# MSB.net
KiCad netlist of a schematic drawn in EasyEDA Pro
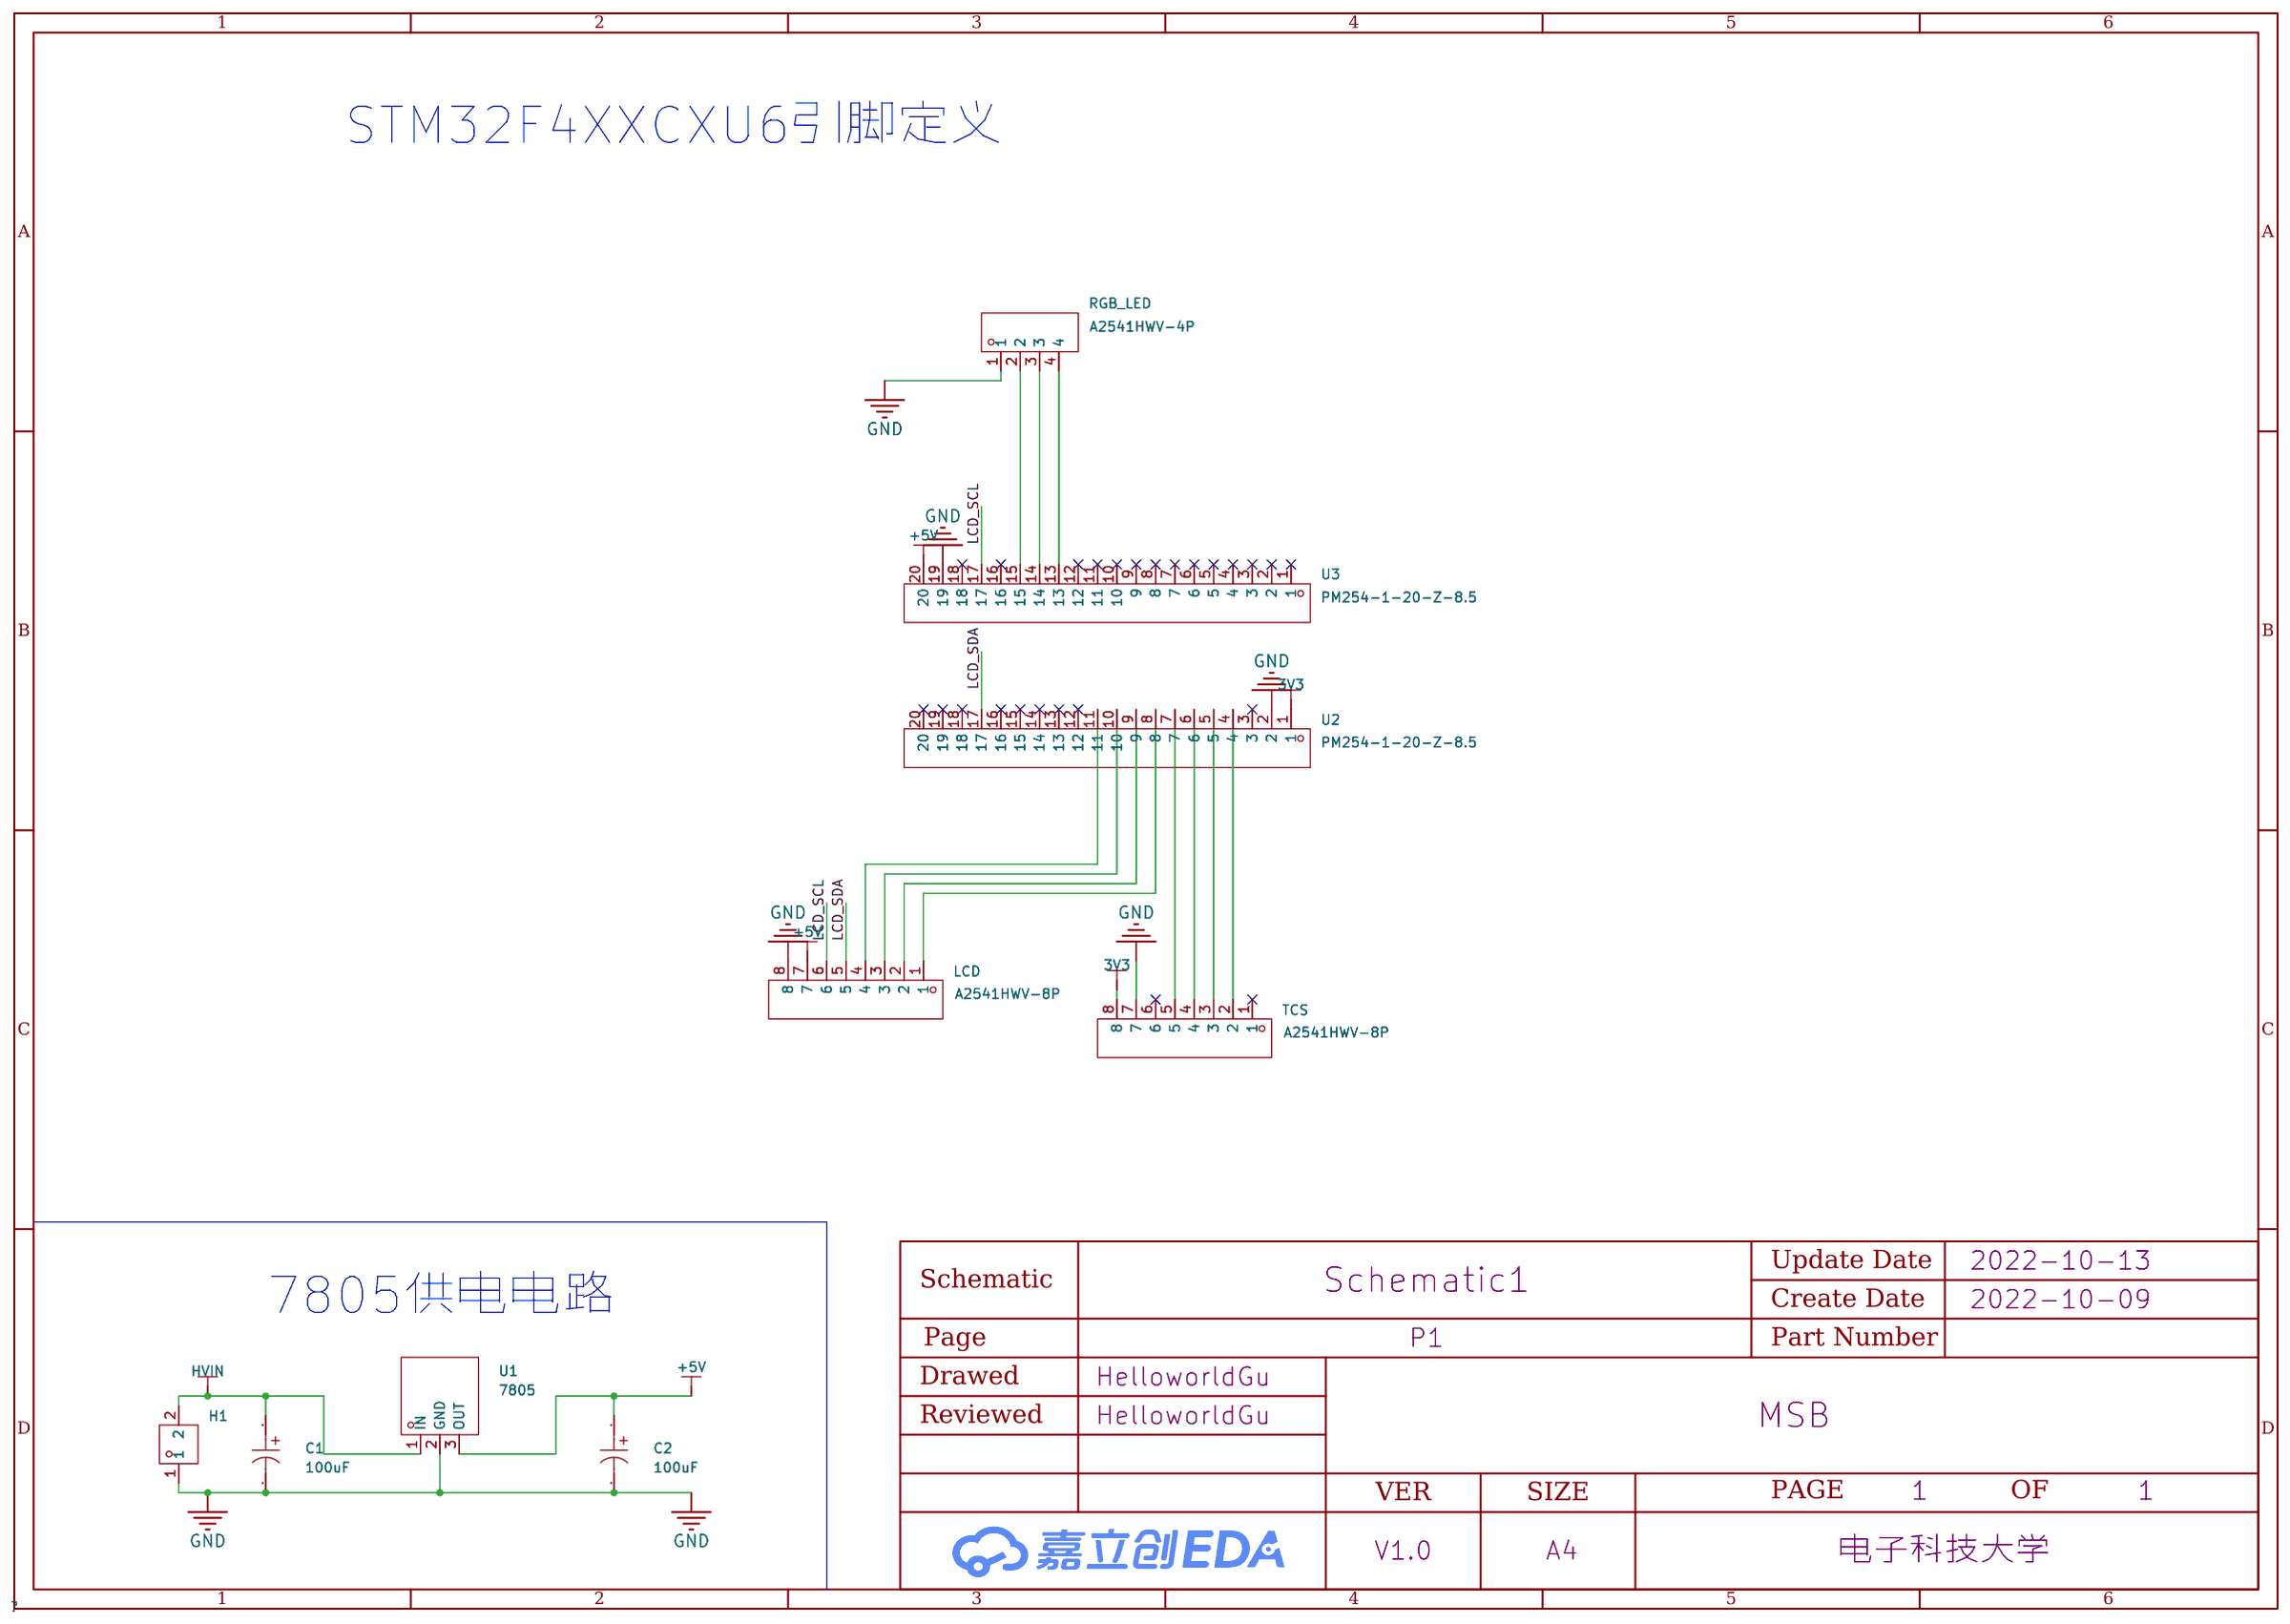
[diagram p0: schematic sheet]

(export (version "E")
  (design (tool "Eeschema 10.0.6"))
  (components
    (comp (ref "C1")
      (value "100uF")
      (footprint "easyedapro:CAP-TH_BD6.3-P2.50-D0.5-FD")
      (description "容值:100uF;精度:±20%;额定电压:35V;电容体直径:-;电容体长度:-;脚间距:-;纹波电流:-;等效串联电阻:-;工作寿命:-;")
      (fields
        (field (name "Manufacturer Part") "ECF1VM101E12OTPO")
        (field (name "Manufacturer") "Yunxing(云星)")
      )
      (libsource (lib "easyedapro") (part "ECF1VM101E12OTPO"))
    )
    (comp (ref "C2")
      (value "100uF")
      (footprint "easyedapro:CAP-TH_BD6.3-P2.50-D0.5-FD")
      (description "容值:100uF;精度:±20%;额定电压:35V;电容体直径:-;电容体长度:-;脚间距:-;纹波电流:-;等效串联电阻:-;工作寿命:-;")
      (fields
        (field (name "Manufacturer Part") "ECF1VM101E12OTPO")
        (field (name "Manufacturer") "Yunxing(云星)")
      )
      (libsource (lib "easyedapro") (part "ECF1VM101E12OTPO"))
    )
    (comp (ref "H1")
      (value "X6521WV-2x01H-C30D60")
      (footprint "easyedapro:HDR-TH_2P-P2.54-V-M")
      (fields (field (name "Manufacturer") "XKB Connectivity(中国星坤)"))
      (libsource (lib "easyedapro") (part "X6521WV-2X01H-C30D60"))
    )
    (comp (ref "LCD")
      (value "A2541HWV-8P")
      (footprint "easyedapro:HDR-TH_8P-P2.54-V-F")
      (fields (field (name "Manufacturer") "CJT(长江连接器)"))
      (libsource (lib "easyedapro") (part "A2541HWV-8P_C5149225"))
    )
    (comp (ref "RGB_LED")
      (value "A2541HWV-4P")
      (footprint "easyedapro:HDR-TH_4P-P2.54-V-F")
      (fields (field (name "Manufacturer") "CJT(长江连接器)"))
      (libsource (lib "easyedapro") (part "A2541HWV-4P_C5176037"))
    )
    (comp (ref "TCS")
      (value "A2541HWV-8P")
      (footprint "easyedapro:HDR-TH_8P-P2.54-V-F")
      (fields (field (name "Manufacturer") "CJT(长江连接器)"))
      (libsource (lib "easyedapro") (part "A2541HWV-8P_C5149225"))
    )
    (comp (ref "U1")
      (value "7805")
      (footprint "easyedapro:TO-220-3_L10.2-W4.5-P2.54-L-1")
      (fields (field (name "Manufacturer") "SY(顺烨）"))
      (libsource (lib "easyedapro") (part "7805_C4944936"))
    )
    (comp (ref "U2")
      (value "PM254-1-20-Z-8.5")
      (footprint "easyedapro:HDR-TH_20P-P2.54-V-F-2")
      (fields (field (name "Manufacturer") "HCTL(华灿天禄)"))
      (libsource (lib "easyedapro") (part "PM254-1-20-Z-8.5"))
    )
    (comp (ref "U3")
      (value "PM254-1-20-Z-8.5")
      (footprint "easyedapro:HDR-TH_20P-P2.54-V-F-2")
      (fields (field (name "Manufacturer") "HCTL(华灿天禄)"))
      (libsource (lib "easyedapro") (part "PM254-1-20-Z-8.5"))
    )
  )
  (nets
    (net (code "1") (name "+5V") (class "Default")
      (node (ref "C2") (pin "1") (pinfunction "1_1") (pintype "input"))
      (node (ref "LCD") (pin "7") (pinfunction "7_7") (pintype "input"))
      (node (ref "U1") (pin "3") (pinfunction "OUT_3") (pintype "input"))
      (node (ref "U3") (pin "20") (pinfunction "20_20") (pintype "input"))
    )
    (net (code "2") (name "/LCD_SCL") (class "Default")
      (node (ref "LCD") (pin "6") (pinfunction "6_6") (pintype "input"))
      (node (ref "U3") (pin "17") (pinfunction "17_17") (pintype "input"))
    )
    (net (code "3") (name "/LCD_SDA") (class "Default")
      (node (ref "LCD") (pin "5") (pinfunction "5_5") (pintype "input"))
      (node (ref "U2") (pin "17") (pinfunction "17_17") (pintype "input"))
    )
    (net (code "4") (name "3V3") (class "Default")
      (node (ref "TCS") (pin "8") (pinfunction "8_8") (pintype "input"))
      (node (ref "U2") (pin "1") (pinfunction "1_1") (pintype "input"))
    )
    (net (code "5") (name "GND") (class "Default")
      (node (ref "C1") (pin "2") (pinfunction "2_2") (pintype "input"))
      (node (ref "C2") (pin "2") (pinfunction "2_2") (pintype "input"))
      (node (ref "H1") (pin "1") (pinfunction "1_1") (pintype "input"))
      (node (ref "LCD") (pin "8") (pinfunction "8_8") (pintype "input"))
      (node (ref "RGB_LED") (pin "1") (pinfunction "1_1") (pintype "input"))
      (node (ref "TCS") (pin "7") (pinfunction "7_7") (pintype "input"))
      (node (ref "U1") (pin "2") (pinfunction "GND_2") (pintype "input"))
      (node (ref "U2") (pin "2") (pinfunction "2_2") (pintype "input"))
      (node (ref "U3") (pin "19") (pinfunction "19_19") (pintype "input"))
    )
    (net (code "6") (name "HVIN") (class "Default")
      (node (ref "C1") (pin "1") (pinfunction "1_1") (pintype "input"))
      (node (ref "H1") (pin "2") (pinfunction "2_2") (pintype "input"))
      (node (ref "U1") (pin "1") (pinfunction "IN_1") (pintype "input"))
    )
    (net (code "7") (name "Net-(LCD-Pad1)") (class "Default")
      (node (ref "LCD") (pin "1") (pinfunction "1_1") (pintype "input"))
      (node (ref "U2") (pin "8") (pinfunction "8_8") (pintype "input"))
    )
    (net (code "8") (name "Net-(LCD-Pad2)") (class "Default")
      (node (ref "LCD") (pin "2") (pinfunction "2_2") (pintype "input"))
      (node (ref "U2") (pin "9") (pinfunction "9_9") (pintype "input"))
    )
    (net (code "9") (name "Net-(LCD-Pad3)") (class "Default")
      (node (ref "LCD") (pin "3") (pinfunction "3_3") (pintype "input"))
      (node (ref "U2") (pin "10") (pinfunction "10_10") (pintype "input"))
    )
    (net (code "10") (name "Net-(LCD-Pad4)") (class "Default")
      (node (ref "LCD") (pin "4") (pinfunction "4_4") (pintype "input"))
      (node (ref "U2") (pin "11") (pinfunction "11_11") (pintype "input"))
    )
    (net (code "11") (name "Net-(RGB_LED-Pad2)") (class "Default")
      (node (ref "RGB_LED") (pin "2") (pinfunction "2_2") (pintype "input"))
      (node (ref "U3") (pin "15") (pinfunction "15_15") (pintype "input"))
    )
    (net (code "12") (name "Net-(RGB_LED-Pad3)") (class "Default")
      (node (ref "RGB_LED") (pin "3") (pinfunction "3_3") (pintype "input"))
      (node (ref "U3") (pin "14") (pinfunction "14_14") (pintype "input"))
    )
    (net (code "13") (name "Net-(RGB_LED-Pad4)") (class "Default")
      (node (ref "RGB_LED") (pin "4") (pinfunction "4_4") (pintype "input"))
      (node (ref "U3") (pin "13") (pinfunction "13_13") (pintype "input"))
    )
    (net (code "14") (name "Net-(TCS-Pad2)") (class "Default")
      (node (ref "TCS") (pin "2") (pinfunction "2_2") (pintype "input"))
      (node (ref "U2") (pin "4") (pinfunction "4_4") (pintype "input"))
    )
    (net (code "15") (name "Net-(TCS-Pad3)") (class "Default")
      (node (ref "TCS") (pin "3") (pinfunction "3_3") (pintype "input"))
      (node (ref "U2") (pin "5") (pinfunction "5_5") (pintype "input"))
    )
    (net (code "16") (name "Net-(TCS-Pad4)") (class "Default")
      (node (ref "TCS") (pin "4") (pinfunction "4_4") (pintype "input"))
      (node (ref "U2") (pin "6") (pinfunction "6_6") (pintype "input"))
    )
    (net (code "17") (name "Net-(TCS-Pad5)") (class "Default")
      (node (ref "TCS") (pin "5") (pinfunction "5_5") (pintype "input"))
      (node (ref "U2") (pin "7") (pinfunction "7_7") (pintype "input"))
    )
    (net (code "18") (name "unconnected-(TCS-Pad1)") (class "Default")
      (node (ref "TCS") (pin "1") (pinfunction "1_1") (pintype "input+no_connect"))
    )
    (net (code "19") (name "unconnected-(TCS-Pad6)") (class "Default")
      (node (ref "TCS") (pin "6") (pinfunction "6_6") (pintype "input+no_connect"))
    )
    (net (code "20") (name "unconnected-(U2-Pad3)") (class "Default")
      (node (ref "U2") (pin "3") (pinfunction "3_3") (pintype "input+no_connect"))
    )
    (net (code "21") (name "unconnected-(U2-Pad12)") (class "Default")
      (node (ref "U2") (pin "12") (pinfunction "12_12") (pintype "input+no_connect"))
    )
    (net (code "22") (name "unconnected-(U2-Pad13)") (class "Default")
      (node (ref "U2") (pin "13") (pinfunction "13_13") (pintype "input+no_connect"))
    )
    (net (code "23") (name "unconnected-(U2-Pad14)") (class "Default")
      (node (ref "U2") (pin "14") (pinfunction "14_14") (pintype "input+no_connect"))
    )
    (net (code "24") (name "unconnected-(U2-Pad15)") (class "Default")
      (node (ref "U2") (pin "15") (pinfunction "15_15") (pintype "input+no_connect"))
    )
    (net (code "25") (name "unconnected-(U2-Pad16)") (class "Default")
      (node (ref "U2") (pin "16") (pinfunction "16_16") (pintype "input+no_connect"))
    )
    (net (code "26") (name "unconnected-(U2-Pad18)") (class "Default")
      (node (ref "U2") (pin "18") (pinfunction "18_18") (pintype "input+no_connect"))
    )
    (net (code "27") (name "unconnected-(U2-Pad19)") (class "Default")
      (node (ref "U2") (pin "19") (pinfunction "19_19") (pintype "input+no_connect"))
    )
    (net (code "28") (name "unconnected-(U2-Pad20)") (class "Default")
      (node (ref "U2") (pin "20") (pinfunction "20_20") (pintype "input+no_connect"))
    )
    (net (code "29") (name "unconnected-(U3-Pad1)") (class "Default")
      (node (ref "U3") (pin "1") (pinfunction "1_1") (pintype "input+no_connect"))
    )
    (net (code "30") (name "unconnected-(U3-Pad2)") (class "Default")
      (node (ref "U3") (pin "2") (pinfunction "2_2") (pintype "input+no_connect"))
    )
    (net (code "31") (name "unconnected-(U3-Pad3)") (class "Default")
      (node (ref "U3") (pin "3") (pinfunction "3_3") (pintype "input+no_connect"))
    )
    (net (code "32") (name "unconnected-(U3-Pad4)") (class "Default")
      (node (ref "U3") (pin "4") (pinfunction "4_4") (pintype "input+no_connect"))
    )
    (net (code "33") (name "unconnected-(U3-Pad5)") (class "Default")
      (node (ref "U3") (pin "5") (pinfunction "5_5") (pintype "input+no_connect"))
    )
    (net (code "34") (name "unconnected-(U3-Pad6)") (class "Default")
      (node (ref "U3") (pin "6") (pinfunction "6_6") (pintype "input+no_connect"))
    )
    (net (code "35") (name "unconnected-(U3-Pad7)") (class "Default")
      (node (ref "U3") (pin "7") (pinfunction "7_7") (pintype "input+no_connect"))
    )
    (net (code "36") (name "unconnected-(U3-Pad8)") (class "Default")
      (node (ref "U3") (pin "8") (pinfunction "8_8") (pintype "input+no_connect"))
    )
    (net (code "37") (name "unconnected-(U3-Pad9)") (class "Default")
      (node (ref "U3") (pin "9") (pinfunction "9_9") (pintype "input+no_connect"))
    )
    (net (code "38") (name "unconnected-(U3-Pad10)") (class "Default")
      (node (ref "U3") (pin "10") (pinfunction "10_10") (pintype "input+no_connect"))
    )
    (net (code "39") (name "unconnected-(U3-Pad11)") (class "Default")
      (node (ref "U3") (pin "11") (pinfunction "11_11") (pintype "input+no_connect"))
    )
    (net (code "40") (name "unconnected-(U3-Pad12)") (class "Default")
      (node (ref "U3") (pin "12") (pinfunction "12_12") (pintype "input+no_connect"))
    )
    (net (code "41") (name "unconnected-(U3-Pad16)") (class "Default")
      (node (ref "U3") (pin "16") (pinfunction "16_16") (pintype "input+no_connect"))
    )
    (net (code "42") (name "unconnected-(U3-Pad18)") (class "Default")
      (node (ref "U3") (pin "18") (pinfunction "18_18") (pintype "input+no_connect"))
    )
  )
)
